# PARADAS_-02.net
KiCad netlist of a schematic drawn in EAGLE
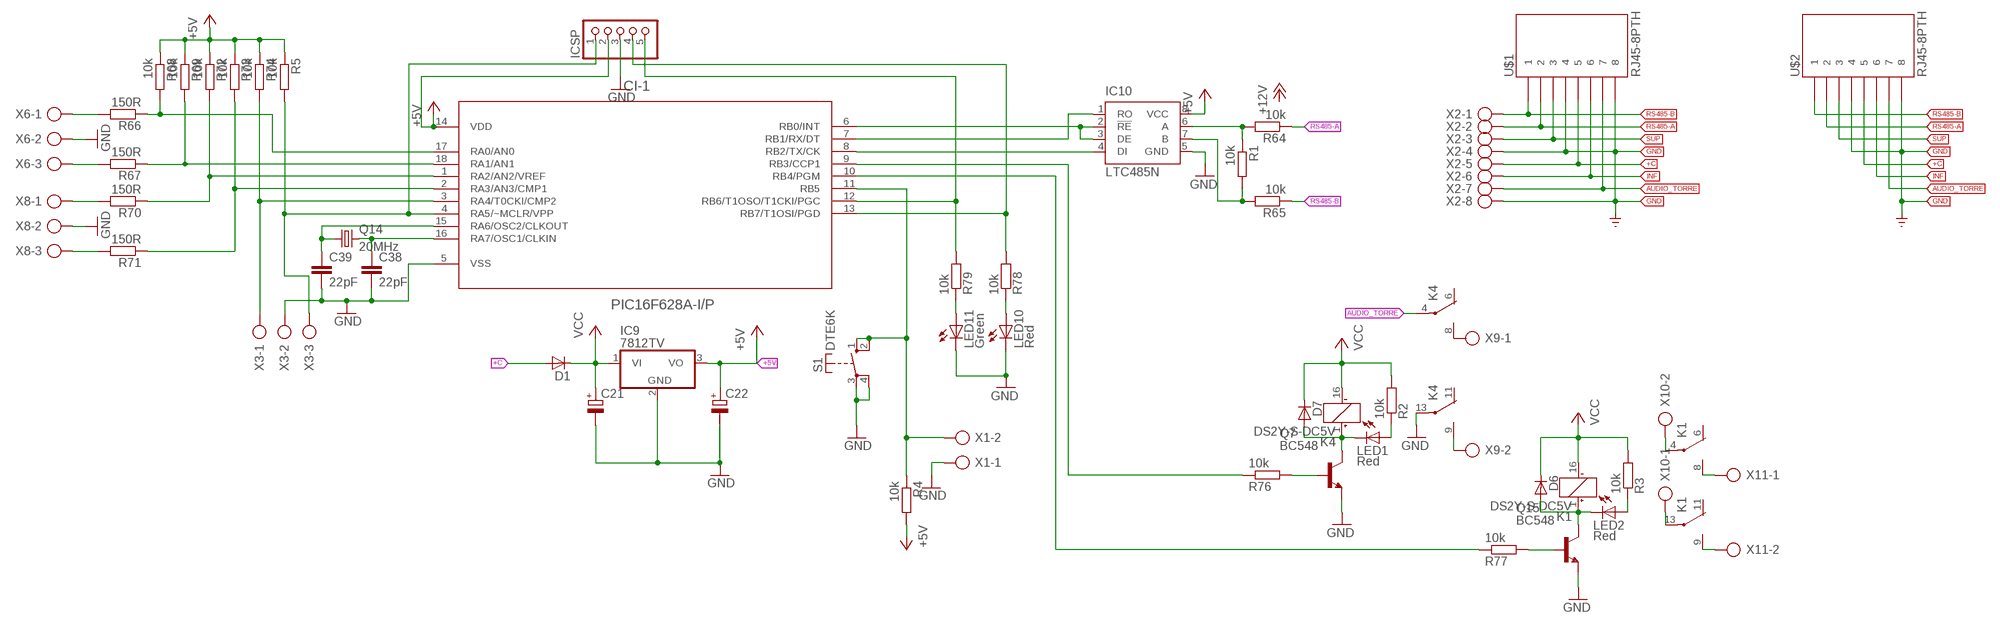
[diagram p0: schematic, sheet 1]

(export (version "E")
  (design (tool "Eeschema 10.0.6"))
  (components
    (comp (ref "C21")
      (value "CPOL-EUE5-13")
      (footprint "eagle-import:E5-13")
      (libsource (lib "eagle-import") (part "CPOL-EUE5-13"))
    )
    (comp (ref "C22")
      (value "CPOL-EUE5-13")
      (footprint "eagle-import:E5-13")
      (libsource (lib "eagle-import") (part "CPOL-EUE5-13"))
    )
    (comp (ref "C38")
      (value "22pF")
      (footprint "eagle-import:C0805")
      (libsource (lib "eagle-import") (part "C-EUC0805"))
    )
    (comp (ref "C39")
      (value "22pF")
      (footprint "eagle-import:C0805")
      (libsource (lib "eagle-import") (part "C-EUC0805"))
    )
    (comp (ref "CI-1")
      (value "PIC16F628A-I/P")
      (footprint "eagle-import:DIP254P762X533-18")
      (libsource (lib "eagle-import") (part "PIC16F628A-I/P"))
    )
    (comp (ref "D1")
      (value "BYS10")
      (footprint "eagle-import:SOD106A")
      (fields (field (name "MPN") "BYS10/45"))
      (libsource (lib "eagle-import") (part "BYS10"))
    )
    (comp (ref "D6")
      (value "BYS10")
      (footprint "eagle-import:SOD106A")
      (fields (field (name "MPN") "BYS10/45"))
      (libsource (lib "eagle-import") (part "BYS10"))
    )
    (comp (ref "D7")
      (value "BYS10")
      (footprint "eagle-import:SOD106A")
      (fields (field (name "MPN") "BYS10/45"))
      (libsource (lib "eagle-import") (part "BYS10"))
    )
    (comp (ref "IC9")
      (value "7812TV")
      (footprint "eagle-import:TO220V")
      (libsource (lib "eagle-import") (part "78TV12"))
    )
    (comp (ref "IC10")
      (value "LTC485N")
      (footprint "eagle-import:DIL08")
      (libsource (lib "eagle-import") (part "LTC485N"))
    )
    (comp (ref "ICSP")
      (value "PINHD-1X5")
      (footprint "eagle-import:1X05")
      (libsource (lib "eagle-import") (part "PINHD-1X5"))
    )
    (comp (ref "K1")
      (value "DS2Y-S-DC5V")
      (footprint "eagle-import:DS2Y")
      (libsource (lib "eagle-import") (part "DS2Y-S-DC5V"))
    )
    (comp (ref "K4")
      (value "DS2Y-S-DC5V")
      (footprint "eagle-import:DS2Y")
      (libsource (lib "eagle-import") (part "DS2Y-S-DC5V"))
    )
    (comp (ref "LED1")
      (value "Red")
      (footprint "eagle-import:LED5MM")
      (libsource (lib "eagle-import") (part "LED5MM"))
    )
    (comp (ref "LED2")
      (value "Red")
      (footprint "eagle-import:LED5MM")
      (libsource (lib "eagle-import") (part "LED5MM"))
    )
    (comp (ref "LED10")
      (value "Red")
      (footprint "eagle-import:LED5MM")
      (libsource (lib "eagle-import") (part "LED5MM"))
    )
    (comp (ref "LED11")
      (value "Green")
      (footprint "eagle-import:LED5MM")
      (libsource (lib "eagle-import") (part "LED5MM"))
    )
    (comp (ref "Q7")
      (value "BC548")
      (footprint "eagle-import:TO92-EBC")
      (libsource (lib "eagle-import") (part "BC548"))
    )
    (comp (ref "Q14")
      (value "20MHz")
      (footprint "eagle-import:HC18U-V")
      (libsource (lib "eagle-import") (part "CRYTALHC18U-V"))
    )
    (comp (ref "Q15")
      (value "BC548")
      (footprint "eagle-import:TO92-EBC")
      (libsource (lib "eagle-import") (part "BC548"))
    )
    (comp (ref "R1")
      (value "10k")
      (footprint "eagle-import:0207_10")
      (libsource (lib "eagle-import") (part "R-EU_0207/10"))
    )
    (comp (ref "R2")
      (value "10k")
      (footprint "eagle-import:0207_10")
      (libsource (lib "eagle-import") (part "R-EU_0207/10"))
    )
    (comp (ref "R3")
      (value "10k")
      (footprint "eagle-import:0207_10")
      (libsource (lib "eagle-import") (part "R-EU_0207/10"))
    )
    (comp (ref "R4")
      (value "10k")
      (footprint "eagle-import:0207_10")
      (libsource (lib "eagle-import") (part "R-EU_0207/10"))
    )
    (comp (ref "R5")
      (value "10k")
      (footprint "eagle-import:0207_10")
      (libsource (lib "eagle-import") (part "R-EU_0207/10"))
    )
    (comp (ref "R64")
      (value "10k")
      (footprint "eagle-import:0207_10")
      (libsource (lib "eagle-import") (part "R-EU_0207/10"))
    )
    (comp (ref "R65")
      (value "10k")
      (footprint "eagle-import:0207_10")
      (libsource (lib "eagle-import") (part "R-EU_0207/10"))
    )
    (comp (ref "R66")
      (value "150R")
      (footprint "eagle-import:0207_10")
      (libsource (lib "eagle-import") (part "R-EU_0207/10"))
    )
    (comp (ref "R67")
      (value "150R")
      (footprint "eagle-import:0207_10")
      (libsource (lib "eagle-import") (part "R-EU_0207/10"))
    )
    (comp (ref "R68")
      (value "10k")
      (footprint "eagle-import:0207_10")
      (libsource (lib "eagle-import") (part "R-EU_0207/10"))
    )
    (comp (ref "R69")
      (value "10k")
      (footprint "eagle-import:0207_10")
      (libsource (lib "eagle-import") (part "R-EU_0207/10"))
    )
    (comp (ref "R70")
      (value "150R")
      (footprint "eagle-import:0207_10")
      (libsource (lib "eagle-import") (part "R-EU_0207/10"))
    )
    (comp (ref "R71")
      (value "150R")
      (footprint "eagle-import:0207_10")
      (libsource (lib "eagle-import") (part "R-EU_0207/10"))
    )
    (comp (ref "R72")
      (value "10k")
      (footprint "eagle-import:0207_10")
      (libsource (lib "eagle-import") (part "R-EU_0207/10"))
    )
    (comp (ref "R73")
      (value "10k")
      (footprint "eagle-import:0207_10")
      (libsource (lib "eagle-import") (part "R-EU_0207/10"))
    )
    (comp (ref "R74")
      (value "10k")
      (footprint "eagle-import:0207_10")
      (libsource (lib "eagle-import") (part "R-EU_0207/10"))
    )
    (comp (ref "R76")
      (value "10k")
      (footprint "eagle-import:0207_10")
      (libsource (lib "eagle-import") (part "R-EU_0207/10"))
    )
    (comp (ref "R77")
      (value "10k")
      (footprint "eagle-import:0207_10")
      (libsource (lib "eagle-import") (part "R-EU_0207/10"))
    )
    (comp (ref "R78")
      (value "10k")
      (footprint "eagle-import:0207_10")
      (libsource (lib "eagle-import") (part "R-EU_0207/10"))
    )
    (comp (ref "R79")
      (value "10k")
      (footprint "eagle-import:0207_10")
      (libsource (lib "eagle-import") (part "R-EU_0207/10"))
    )
    (comp (ref "S1")
      (value "DTE6K")
      (footprint "eagle-import:DTE6K")
      (libsource (lib "eagle-import") (part "DTE6K"))
    )
    (comp (ref "U$1")
      (value "RJ45-8PTH")
      (footprint "eagle-import:RJ45-8")
      (libsource (lib "eagle-import") (part "RJ45-8PTH"))
    )
    (comp (ref "U$2")
      (value "RJ45-8PTH")
      (footprint "eagle-import:RJ45-8")
      (libsource (lib "eagle-import") (part "RJ45-8PTH"))
    )
    (comp (ref "X1")
      (value "AK500/2")
      (footprint "eagle-import:AK500_2")
      (libsource (lib "eagle-import") (part "AK500/2"))
    )
    (comp (ref "X2")
      (value "RS485_CNT")
      (footprint "eagle-import:AK500_8")
      (libsource (lib "eagle-import") (part "AK500/8"))
    )
    (comp (ref "X3")
      (value "AK500/3")
      (footprint "eagle-import:AK500_3")
      (libsource (lib "eagle-import") (part "AK500/3"))
    )
    (comp (ref "X6")
      (value "AK500/3")
      (footprint "eagle-import:AK500_3")
      (libsource (lib "eagle-import") (part "AK500/3"))
    )
    (comp (ref "X8")
      (value "AK500/3")
      (footprint "eagle-import:AK500_3")
      (libsource (lib "eagle-import") (part "AK500/3"))
    )
    (comp (ref "X9")
      (value "AK500/2")
      (footprint "eagle-import:AK500_2")
      (libsource (lib "eagle-import") (part "AK500/2"))
    )
    (comp (ref "X10")
      (value "AK500/2")
      (footprint "eagle-import:AK500_2")
      (libsource (lib "eagle-import") (part "AK500/2"))
    )
    (comp (ref "X11")
      (value "AK500/2")
      (footprint "eagle-import:AK500_2")
      (libsource (lib "eagle-import") (part "AK500/2"))
    )
  )
  (nets
    (net (code "1") (name "+5V") (class "Default")
      (node (ref "C22") (pin "+") (pinfunction "+_+") (pintype "passive"))
      (node (ref "CI-1") (pin "14") (pinfunction "VDD_14") (pintype "power_in"))
      (node (ref "IC10") (pin "8") (pinfunction "VCC_8") (pintype "input"))
      (node (ref "IC9") (pin "3") (pinfunction "VO_3") (pintype "passive"))
      (node (ref "ICSP") (pin "2") (pinfunction "2_2") (pintype "passive"))
      (node (ref "R4") (pin "2") (pinfunction "2_2") (pintype "passive"))
      (node (ref "R5") (pin "1") (pinfunction "1_1") (pintype "passive"))
      (node (ref "R68") (pin "1") (pinfunction "1_1") (pintype "passive"))
      (node (ref "R69") (pin "1") (pinfunction "1_1") (pintype "passive"))
      (node (ref "R72") (pin "1") (pinfunction "1_1") (pintype "passive"))
      (node (ref "R73") (pin "1") (pinfunction "1_1") (pintype "passive"))
      (node (ref "R74") (pin "1") (pinfunction "1_1") (pintype "passive"))
    )
    (net (code "3") (name "+C") (class "Default")
      (node (ref "D1") (pin "A") (pinfunction "A_A") (pintype "passive"))
      (node (ref "U$1") (pin "5") (pinfunction "5_5") (pintype "bidirectional"))
      (node (ref "U$2") (pin "5") (pinfunction "5_5") (pintype "bidirectional"))
      (node (ref "X2") (pin "5") (pinfunction "KL_5") (pintype "passive"))
    )
    (net (code "4") (name "AUDIO_TORRE") (class "Default")
      (node (ref "K4") (pin "4") (pinfunction "P_4") (pintype "passive"))
      (node (ref "U$1") (pin "7") (pinfunction "7_7") (pintype "bidirectional"))
      (node (ref "U$2") (pin "7") (pinfunction "7_7") (pintype "bidirectional"))
      (node (ref "X2") (pin "7") (pinfunction "KL_7") (pintype "passive"))
    )
    (net (code "5") (name "GND") (class "Default")
      (node (ref "C21") (pin "-") (pinfunction "-_-") (pintype "passive"))
      (node (ref "C22") (pin "-") (pinfunction "-_-") (pintype "passive"))
      (node (ref "C38") (pin "2") (pinfunction "2_2") (pintype "passive"))
      (node (ref "C39") (pin "2") (pinfunction "2_2") (pintype "passive"))
      (node (ref "CI-1") (pin "5") (pinfunction "VSS_5") (pintype "power_in"))
      (node (ref "IC10") (pin "5") (pinfunction "GND_5") (pintype "input"))
      (node (ref "IC9") (pin "2") (pinfunction "GND_2") (pintype "passive"))
      (node (ref "ICSP") (pin "3") (pinfunction "3_3") (pintype "passive"))
      (node (ref "K4") (pin "13") (pinfunction "P_13") (pintype "passive"))
      (node (ref "LED10") (pin "K") (pinfunction "C_K") (pintype "passive"))
      (node (ref "LED11") (pin "K") (pinfunction "C_K") (pintype "passive"))
      (node (ref "Q15") (pin "E") (pinfunction "E_E") (pintype "passive"))
      (node (ref "Q7") (pin "E") (pinfunction "E_E") (pintype "passive"))
      (node (ref "S1") (pin "3") (pinfunction "P_3") (pintype "passive"))
      (node (ref "S1") (pin "4") (pinfunction "P_4") (pintype "passive"))
      (node (ref "U$1") (pin "4") (pinfunction "4_4") (pintype "bidirectional"))
      (node (ref "U$1") (pin "8") (pinfunction "8_8") (pintype "bidirectional"))
      (node (ref "U$2") (pin "4") (pinfunction "4_4") (pintype "bidirectional"))
      (node (ref "U$2") (pin "8") (pinfunction "8_8") (pintype "bidirectional"))
      (node (ref "X1") (pin "1") (pinfunction "KL_1") (pintype "passive"))
      (node (ref "X2") (pin "4") (pinfunction "KL_4") (pintype "passive"))
      (node (ref "X2") (pin "8") (pinfunction "KL_8") (pintype "passive"))
      (node (ref "X3") (pin "2") (pinfunction "KL_2") (pintype "passive"))
      (node (ref "X6") (pin "2") (pinfunction "KL_2") (pintype "passive"))
      (node (ref "X8") (pin "2") (pinfunction "KL_2") (pintype "passive"))
    )
    (net (code "6") (name "INF") (class "Default")
      (node (ref "U$1") (pin "6") (pinfunction "6_6") (pintype "bidirectional"))
      (node (ref "U$2") (pin "6") (pinfunction "6_6") (pintype "bidirectional"))
      (node (ref "X2") (pin "6") (pinfunction "KL_6") (pintype "passive"))
    )
    (net (code "7") (name "Net-(CI-1-RA0{slash}AN0)") (class "Default")
      (node (ref "CI-1") (pin "17") (pinfunction "RA0/AN0_17") (pintype "bidirectional"))
      (node (ref "R66") (pin "1") (pinfunction "1_1") (pintype "passive"))
      (node (ref "R68") (pin "2") (pinfunction "2_2") (pintype "passive"))
    )
    (net (code "8") (name "Net-(CI-1-RA1{slash}AN1)") (class "Default")
      (node (ref "CI-1") (pin "18") (pinfunction "RA1/AN1_18") (pintype "bidirectional"))
      (node (ref "R67") (pin "1") (pinfunction "1_1") (pintype "passive"))
      (node (ref "R69") (pin "2") (pinfunction "2_2") (pintype "passive"))
    )
    (net (code "9") (name "Net-(CI-1-RA2{slash}AN2{slash}VREF)") (class "Default")
      (node (ref "CI-1") (pin "1") (pinfunction "RA2/AN2/VREF_1") (pintype "bidirectional"))
      (node (ref "R70") (pin "1") (pinfunction "1_1") (pintype "passive"))
      (node (ref "R72") (pin "2") (pinfunction "2_2") (pintype "passive"))
    )
    (net (code "10") (name "Net-(CI-1-RA3{slash}AN3{slash}CMP1)") (class "Default")
      (node (ref "CI-1") (pin "2") (pinfunction "RA3/AN3/CMP1_2") (pintype "bidirectional"))
      (node (ref "R71") (pin "1") (pinfunction "1_1") (pintype "passive"))
      (node (ref "R73") (pin "2") (pinfunction "2_2") (pintype "passive"))
    )
    (net (code "11") (name "Net-(CI-1-RA4{slash}T0CKI{slash}CMP2)") (class "Default")
      (node (ref "CI-1") (pin "3") (pinfunction "RA4/T0CKI/CMP2_3") (pintype "bidirectional"))
      (node (ref "R74") (pin "2") (pinfunction "2_2") (pintype "passive"))
      (node (ref "X3") (pin "1") (pinfunction "KL_1") (pintype "passive"))
    )
    (net (code "12") (name "Net-(CI-1-RA5{slash}~{MCLR{slash}VPP})") (class "Default")
      (node (ref "CI-1") (pin "4") (pinfunction "RA5/~{MCLR/VPP}_4") (pintype "bidirectional"))
      (node (ref "ICSP") (pin "1") (pinfunction "1_1") (pintype "passive"))
      (node (ref "R5") (pin "2") (pinfunction "2_2") (pintype "passive"))
      (node (ref "X3") (pin "3") (pinfunction "KL_3") (pintype "passive"))
    )
    (net (code "13") (name "Net-(CI-1-RA6{slash}OSC2{slash}CLKOUT)") (class "Default")
      (node (ref "C39") (pin "1") (pinfunction "1_1") (pintype "passive"))
      (node (ref "CI-1") (pin "15") (pinfunction "RA6/OSC2/CLKOUT_15") (pintype "bidirectional"))
      (node (ref "Q14") (pin "1") (pinfunction "1_1") (pintype "passive"))
    )
    (net (code "14") (name "Net-(CI-1-RA7{slash}OSC1{slash}CLKIN)") (class "Default")
      (node (ref "C38") (pin "1") (pinfunction "1_1") (pintype "passive"))
      (node (ref "CI-1") (pin "16") (pinfunction "RA7/OSC1/CLKIN_16") (pintype "bidirectional"))
      (node (ref "Q14") (pin "2") (pinfunction "2_2") (pintype "passive"))
    )
    (net (code "15") (name "Net-(CI-1-RB0{slash}INT)") (class "Default")
      (node (ref "CI-1") (pin "6") (pinfunction "RB0/INT_6") (pintype "bidirectional"))
      (node (ref "IC10") (pin "2") (pinfunction "~{RE}_2") (pintype "input"))
      (node (ref "IC10") (pin "3") (pinfunction "DE_3") (pintype "input"))
    )
    (net (code "16") (name "Net-(CI-1-RB1{slash}RX{slash}DT)") (class "Default")
      (node (ref "CI-1") (pin "7") (pinfunction "RB1/RX/DT_7") (pintype "bidirectional"))
      (node (ref "IC10") (pin "1") (pinfunction "RO_1") (pintype "output"))
    )
    (net (code "17") (name "Net-(CI-1-RB2{slash}TX{slash}CK)") (class "Default")
      (node (ref "CI-1") (pin "8") (pinfunction "RB2/TX/CK_8") (pintype "bidirectional"))
      (node (ref "IC10") (pin "4") (pinfunction "DI_4") (pintype "input"))
    )
    (net (code "18") (name "Net-(CI-1-RB3{slash}CCP1)") (class "Default")
      (node (ref "CI-1") (pin "9") (pinfunction "RB3/CCP1_9") (pintype "bidirectional"))
      (node (ref "R76") (pin "1") (pinfunction "1_1") (pintype "passive"))
    )
    (net (code "19") (name "Net-(CI-1-RB4{slash}PGM)") (class "Default")
      (node (ref "CI-1") (pin "10") (pinfunction "RB4/PGM_10") (pintype "bidirectional"))
      (node (ref "R77") (pin "1") (pinfunction "1_1") (pintype "passive"))
    )
    (net (code "20") (name "Net-(CI-1-RB5)") (class "Default")
      (node (ref "CI-1") (pin "11") (pinfunction "RB5_11") (pintype "bidirectional"))
      (node (ref "R4") (pin "1") (pinfunction "1_1") (pintype "passive"))
      (node (ref "S1") (pin "1") (pinfunction "S_1") (pintype "passive"))
      (node (ref "S1") (pin "2") (pinfunction "S_2") (pintype "passive"))
      (node (ref "X1") (pin "2") (pinfunction "KL_2") (pintype "passive"))
    )
    (net (code "21") (name "Net-(CI-1-RB6{slash}T1OSO{slash}T1CKI{slash}PGC)") (class "Default")
      (node (ref "CI-1") (pin "12") (pinfunction "RB6/T1OSO/T1CKI/PGC_12") (pintype "bidirectional"))
      (node (ref "ICSP") (pin "5") (pinfunction "5_5") (pintype "passive"))
      (node (ref "R79") (pin "2") (pinfunction "2_2") (pintype "passive"))
    )
    (net (code "22") (name "Net-(CI-1-RB7{slash}T1OSI{slash}PGD)") (class "Default")
      (node (ref "CI-1") (pin "13") (pinfunction "RB7/T1OSI/PGD_13") (pintype "bidirectional"))
      (node (ref "ICSP") (pin "4") (pinfunction "4_4") (pintype "passive"))
      (node (ref "R78") (pin "2") (pinfunction "2_2") (pintype "passive"))
    )
    (net (code "23") (name "Net-(IC10-A)") (class "Default")
      (node (ref "IC10") (pin "6") (pinfunction "A_6") (pintype "bidirectional"))
      (node (ref "R1") (pin "1") (pinfunction "1_1") (pintype "passive"))
      (node (ref "R64") (pin "2") (pinfunction "2_2") (pintype "passive"))
    )
    (net (code "24") (name "Net-(IC10-B)") (class "Default")
      (node (ref "IC10") (pin "7") (pinfunction "B_7") (pintype "bidirectional"))
      (node (ref "R1") (pin "2") (pinfunction "2_2") (pintype "passive"))
      (node (ref "R65") (pin "2") (pinfunction "2_2") (pintype "passive"))
    )
    (net (code "25") (name "Net-(K1A-+)") (class "Default")
      (node (ref "D6") (pin "A") (pinfunction "A_A") (pintype "passive"))
      (node (ref "K1") (pin "1") (pinfunction "+_1") (pintype "passive"))
      (node (ref "LED2") (pin "K") (pinfunction "C_K") (pintype "passive"))
      (node (ref "Q15") (pin "C") (pinfunction "C_C") (pintype "passive"))
    )
    (net (code "26") (name "Net-(K1B-P)") (class "Default")
      (node (ref "K1") (pin "4") (pinfunction "P_4") (pintype "passive"))
      (node (ref "X10") (pin "2") (pinfunction "KL_2") (pintype "passive"))
    )
    (net (code "27") (name "Net-(K1B-S)") (class "Default")
      (node (ref "K1") (pin "8") (pinfunction "S_8") (pintype "passive"))
      (node (ref "X11") (pin "1") (pinfunction "KL_1") (pintype "passive"))
    )
    (net (code "28") (name "Net-(K1C-P)") (class "Default")
      (node (ref "K1") (pin "13") (pinfunction "P_13") (pintype "passive"))
      (node (ref "X10") (pin "1") (pinfunction "KL_1") (pintype "passive"))
    )
    (net (code "29") (name "Net-(K1C-S)") (class "Default")
      (node (ref "K1") (pin "9") (pinfunction "S_9") (pintype "passive"))
      (node (ref "X11") (pin "2") (pinfunction "KL_2") (pintype "passive"))
    )
    (net (code "30") (name "Net-(K4A-+)") (class "Default")
      (node (ref "D7") (pin "A") (pinfunction "A_A") (pintype "passive"))
      (node (ref "K4") (pin "1") (pinfunction "+_1") (pintype "passive"))
      (node (ref "LED1") (pin "K") (pinfunction "C_K") (pintype "passive"))
      (node (ref "Q7") (pin "C") (pinfunction "C_C") (pintype "passive"))
    )
    (net (code "31") (name "Net-(K4B-S)") (class "Default")
      (node (ref "K4") (pin "8") (pinfunction "S_8") (pintype "passive"))
      (node (ref "X9") (pin "1") (pinfunction "KL_1") (pintype "passive"))
    )
    (net (code "32") (name "Net-(K4C-S)") (class "Default")
      (node (ref "K4") (pin "9") (pinfunction "S_9") (pintype "passive"))
      (node (ref "X9") (pin "2") (pinfunction "KL_2") (pintype "passive"))
    )
    (net (code "33") (name "Net-(LED1-PadA)") (class "Default")
      (node (ref "LED1") (pin "A") (pinfunction "A_A") (pintype "passive"))
      (node (ref "R2") (pin "1") (pinfunction "1_1") (pintype "passive"))
    )
    (net (code "34") (name "Net-(LED2-PadA)") (class "Default")
      (node (ref "LED2") (pin "A") (pinfunction "A_A") (pintype "passive"))
      (node (ref "R3") (pin "1") (pinfunction "1_1") (pintype "passive"))
    )
    (net (code "35") (name "Net-(LED10-PadA)") (class "Default")
      (node (ref "LED10") (pin "A") (pinfunction "A_A") (pintype "passive"))
      (node (ref "R78") (pin "1") (pinfunction "1_1") (pintype "passive"))
    )
    (net (code "36") (name "Net-(LED11-PadA)") (class "Default")
      (node (ref "LED11") (pin "A") (pinfunction "A_A") (pintype "passive"))
      (node (ref "R79") (pin "1") (pinfunction "1_1") (pintype "passive"))
    )
    (net (code "37") (name "Net-(Q7-PadB)") (class "Default")
      (node (ref "Q7") (pin "B") (pinfunction "B_B") (pintype "passive"))
      (node (ref "R76") (pin "2") (pinfunction "2_2") (pintype "passive"))
    )
    (net (code "38") (name "Net-(Q15-PadB)") (class "Default")
      (node (ref "Q15") (pin "B") (pinfunction "B_B") (pintype "passive"))
      (node (ref "R77") (pin "2") (pinfunction "2_2") (pintype "passive"))
    )
    (net (code "39") (name "Net-(X6A-KL)") (class "Default")
      (node (ref "R66") (pin "2") (pinfunction "2_2") (pintype "passive"))
      (node (ref "X6") (pin "1") (pinfunction "KL_1") (pintype "passive"))
    )
    (net (code "40") (name "Net-(X6C-KL)") (class "Default")
      (node (ref "R67") (pin "2") (pinfunction "2_2") (pintype "passive"))
      (node (ref "X6") (pin "3") (pinfunction "KL_3") (pintype "passive"))
    )
    (net (code "41") (name "Net-(X8A-KL)") (class "Default")
      (node (ref "R70") (pin "2") (pinfunction "2_2") (pintype "passive"))
      (node (ref "X8") (pin "1") (pinfunction "KL_1") (pintype "passive"))
    )
    (net (code "42") (name "Net-(X8C-KL)") (class "Default")
      (node (ref "R71") (pin "2") (pinfunction "2_2") (pintype "passive"))
      (node (ref "X8") (pin "3") (pinfunction "KL_3") (pintype "passive"))
    )
    (net (code "43") (name "RS485-A") (class "Default")
      (node (ref "R64") (pin "1") (pinfunction "1_1") (pintype "passive"))
      (node (ref "U$1") (pin "2") (pinfunction "2_2") (pintype "bidirectional"))
      (node (ref "U$2") (pin "2") (pinfunction "2_2") (pintype "bidirectional"))
      (node (ref "X2") (pin "2") (pinfunction "KL_2") (pintype "passive"))
    )
    (net (code "44") (name "RS485-B") (class "Default")
      (node (ref "R65") (pin "1") (pinfunction "1_1") (pintype "passive"))
      (node (ref "U$1") (pin "1") (pinfunction "1_1") (pintype "bidirectional"))
      (node (ref "U$2") (pin "1") (pinfunction "1_1") (pintype "bidirectional"))
      (node (ref "X2") (pin "1") (pinfunction "KL_1") (pintype "passive"))
    )
    (net (code "45") (name "SUP") (class "Default")
      (node (ref "U$1") (pin "3") (pinfunction "3_3") (pintype "bidirectional"))
      (node (ref "U$2") (pin "3") (pinfunction "3_3") (pintype "bidirectional"))
      (node (ref "X2") (pin "3") (pinfunction "KL_3") (pintype "passive"))
    )
    (net (code "46") (name "VCC") (class "Default")
      (node (ref "C21") (pin "+") (pinfunction "+_+") (pintype "passive"))
      (node (ref "D1") (pin "K") (pinfunction "K_K") (pintype "passive"))
      (node (ref "D6") (pin "K") (pinfunction "K_K") (pintype "passive"))
      (node (ref "D7") (pin "K") (pinfunction "K_K") (pintype "passive"))
      (node (ref "IC9") (pin "1") (pinfunction "VI_1") (pintype "input"))
      (node (ref "K1") (pin "16") (pinfunction "-_16") (pintype "passive"))
      (node (ref "K4") (pin "16") (pinfunction "-_16") (pintype "passive"))
      (node (ref "R2") (pin "2") (pinfunction "2_2") (pintype "passive"))
      (node (ref "R3") (pin "2") (pinfunction "2_2") (pintype "passive"))
    )
    (net (code "47") (name "unconnected-(K1B-O-Pad6)") (class "Default")
      (node (ref "K1") (pin "6") (pinfunction "O_6") (pintype "passive"))
    )
    (net (code "48") (name "unconnected-(K1C-O-Pad11)") (class "Default")
      (node (ref "K1") (pin "11") (pinfunction "O_11") (pintype "passive"))
    )
    (net (code "49") (name "unconnected-(K4B-O-Pad6)") (class "Default")
      (node (ref "K4") (pin "6") (pinfunction "O_6") (pintype "passive"))
    )
    (net (code "50") (name "unconnected-(K4C-O-Pad11)") (class "Default")
      (node (ref "K4") (pin "11") (pinfunction "O_11") (pintype "passive"))
    )
  )
)
